# IoT_Greenhouse_V1_0_A_-_Esp32.net
KiCad netlist of a schematic drawn in Altium Designer
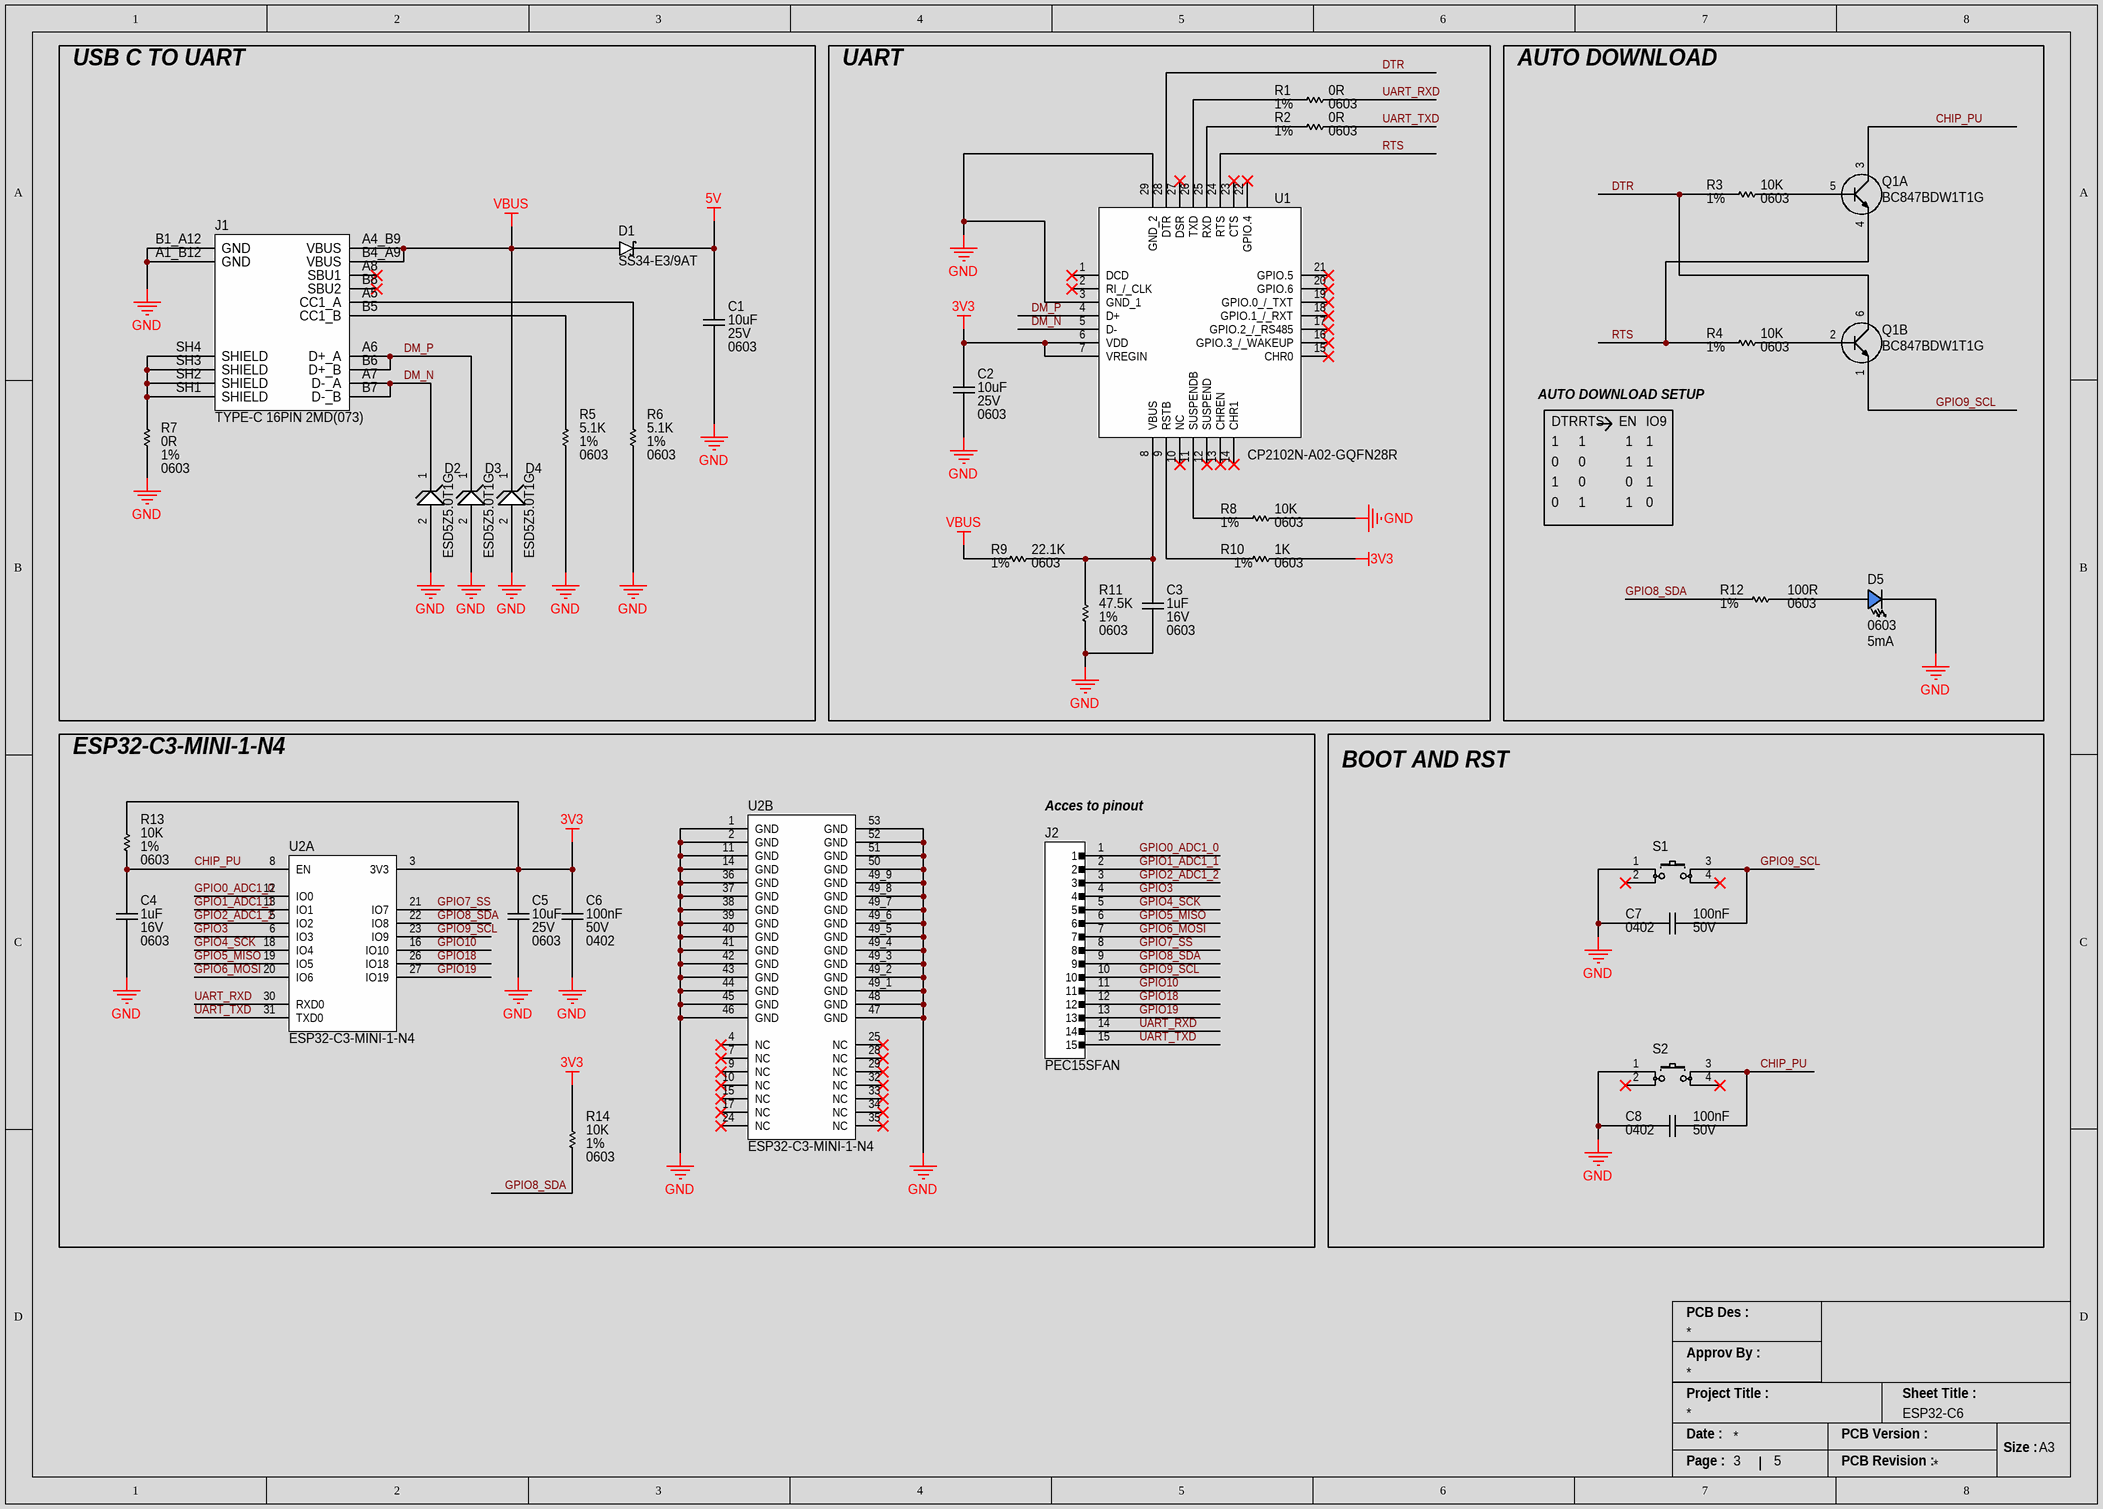
[diagram p0: IoT_Greenhouse V1.0 A - Esp32.SchDoc]

(export (version "E")
  (design (tool "Eeschema 10.0.6"))
  (components
    (comp (ref "C1")
      (value "GRM188R61E106MA73D")
      (footprint "CAP_0603_CAPC1608X08N")
      (description "Multilayer Ceramic Capacitor, 10 uF, 25 V, ± 20%, X5R, 0603 [1608 Metric]")
      (fields
        (field (name "MANUFACTURER") "Murata")
        (field (name "TOLERANCE") "20%")
        (field (name "CASE/PACKAGE") "0603")
        (field (name "CAPACITANCE") "10uF")
        (field (name "VOLTAGE RATING") "25V")
      )
      (libsource (lib "Electronic Devices_LIB") (part "CAP_10UF_25V_X5R_0603"))
    )
    (comp (ref "C2")
      (value "GRM188R61E106MA73D")
      (footprint "CAP_0603_CAPC1608X08N")
      (description "Multilayer Ceramic Capacitor, 10 uF, 25 V, ± 20%, X5R, 0603 [1608 Metric]")
      (fields
        (field (name "MANUFACTURER") "Murata")
        (field (name "TOLERANCE") "20%")
        (field (name "CASE/PACKAGE") "0603")
        (field (name "CAPACITANCE") "10uF")
        (field (name "VOLTAGE RATING") "25V")
      )
      (libsource (lib "Electronic Devices_LIB") (part "CAP_10UF_25V_X5R_0603"))
    )
    (comp (ref "C3")
      (value "CL10A105KO8NNNC")
      (footprint "CAP_0603_CAPC1608X08N")
      (description "CAP CER 1UF 16V X5R 0603")
      (fields
        (field (name "MANUFACTURER") "Samsung")
        (field (name "TOLERANCE") "10%")
        (field (name "VOLTAGE RATING") "16V")
        (field (name "CAPACITANCE") "1uF")
        (field (name "CASE/PACKAGE") "0603")
      )
      (libsource (lib "Electronic Devices_LIB") (part "CAP_1UF_16V_X5R_0603"))
    )
    (comp (ref "C4")
      (value "CL10A105KO8NNNC")
      (footprint "CAP_0603_CAPC1608X08N")
      (description "CAP CER 1UF 16V X5R 0603")
      (fields
        (field (name "MANUFACTURER") "Samsung")
        (field (name "TOLERANCE") "10%")
        (field (name "VOLTAGE RATING") "16V")
        (field (name "CAPACITANCE") "1uF")
        (field (name "CASE/PACKAGE") "0603")
      )
      (libsource (lib "Electronic Devices_LIB") (part "CAP_1UF_16V_X5R_0603"))
    )
    (comp (ref "C5")
      (value "GRM188R61E106MA73D")
      (footprint "CAP_0603_CAPC1608X08N")
      (description "Multilayer Ceramic Capacitor, 10 uF, 25 V, ± 20%, X5R, 0603 [1608 Metric]")
      (fields
        (field (name "MANUFACTURER") "Murata")
        (field (name "TOLERANCE") "20%")
        (field (name "CASE/PACKAGE") "0603")
        (field (name "CAPACITANCE") "10uF")
        (field (name "VOLTAGE RATING") "25V")
      )
      (libsource (lib "Electronic Devices_LIB") (part "CAP_10UF_25V_X5R_0603"))
    )
    (comp (ref "C6")
      (value "GRM155R71H104KE14D")
      (footprint "CAP_0402_CAPC1005X05N")
      (description "Multilayer Ceramic Capacitor, 0.1 uF, 16 V, ± 10%, X7R, 0402 [1005 Metric]")
      (fields
        (field (name "MANUFACTURER") "Murata")
        (field (name "TOLERANCE") "10%")
        (field (name "VOLTAGE RATING") "50V")
        (field (name "CAPACITANCE") "100nF")
        (field (name "CASE/PACKAGE") "0402")
      )
      (libsource (lib "Electronic Devices_LIB") (part "CAP_100NF_50V_X7R_0402"))
    )
    (comp (ref "C7")
      (value "GRM155R71H104KE14D")
      (footprint "CAP_0402_CAPC1005X05N")
      (description "Multilayer Ceramic Capacitor, 0.1 uF, 16 V, ± 10%, X7R, 0402 [1005 Metric]")
      (fields
        (field (name "MANUFACTURER") "Murata")
        (field (name "TOLERANCE") "10%")
        (field (name "VOLTAGE RATING") "50V")
        (field (name "CAPACITANCE") "100nF")
        (field (name "CASE/PACKAGE") "0402")
      )
      (libsource (lib "Electronic Devices_LIB") (part "CAP_100NF_50V_X7R_0402"))
    )
    (comp (ref "C8")
      (value "GRM155R71H104KE14D")
      (footprint "CAP_0402_CAPC1005X05N")
      (description "Multilayer Ceramic Capacitor, 0.1 uF, 16 V, ± 10%, X7R, 0402 [1005 Metric]")
      (fields
        (field (name "MANUFACTURER") "Murata")
        (field (name "TOLERANCE") "10%")
        (field (name "VOLTAGE RATING") "50V")
        (field (name "CAPACITANCE") "100nF")
        (field (name "CASE/PACKAGE") "0402")
      )
      (libsource (lib "Electronic Devices_LIB") (part "CAP_100NF_50V_X7R_0402"))
    )
    (comp (ref "D1")
      (value "SS34-E3/9AT")
      (footprint "DIO_Vishay_SMC_MFG")
      (description "Rectifier Diode, schottky, 40V V(Rrm), do-214Ab / Smc")
      (fields (field (name "MANUFACTURER") "Vishay Semiconductors"))
      (libsource (lib "Electronic Devices_LIB") (part "DIO_SCTKY_40V_3A"))
    )
    (comp (ref "D2")
      (value "ESD5Z5.0T1G")
      (footprint "SOD523_SODFL1608X70N")
      (description "ESD5Z Series 6.2 V 80 pF 5 Vrwm TVS and ESD Protection Diodes - SOD-523")
      (fields (field (name "MANUFACTURER") "ON Semiconductor"))
      (libsource (lib "Electronic Devices_LIB") (part "DIO_TVS_5V_ESD5Z5.0T1G"))
    )
    (comp (ref "D3")
      (value "ESD5Z5.0T1G")
      (footprint "SOD523_SODFL1608X70N")
      (description "ESD5Z Series 6.2 V 80 pF 5 Vrwm TVS and ESD Protection Diodes - SOD-523")
      (fields (field (name "MANUFACTURER") "ON Semiconductor"))
      (libsource (lib "Electronic Devices_LIB") (part "DIO_TVS_5V_ESD5Z5.0T1G"))
    )
    (comp (ref "D4")
      (value "ESD5Z5.0T1G")
      (footprint "SOD523_SODFL1608X70N")
      (description "ESD5Z Series 6.2 V 80 pF 5 Vrwm TVS and ESD Protection Diodes - SOD-523")
      (fields (field (name "MANUFACTURER") "ON Semiconductor"))
      (libsource (lib "Electronic Devices_LIB") (part "DIO_TVS_5V_ESD5Z5.0T1G"))
    )
    (comp (ref "D5")
      (value "LTST-C193TBKT-5A")
      (footprint "LED_0603-BLUE-0.75mm")
      (description "LED Uni-Color Blue 468nm 2-Pin Chip LED T/R")
      (fields
        (field (name "MANUFACTURER") "Vishay Lite-On")
        (field (name "CASE CODE (IMPERIAL)") "0603")
        (field (name "TEST CURRENT") "5mA")
      )
      (libsource (lib "Electronic Devices_LIB") (part "LED_DIO_BLUE_5mA_0603"))
    )
    (comp (ref "J1")
      (value "TYPE-C 16PIN 2MD(073)")
      (footprint "CONN_USB_C_16P")
      (description "5A 1 Surface Mount 16P Female -25℃~+85℃ Type-C SMD USB Connectors ROHS")
      (fields (field (name "MANUFACTURER") "SHOU HAN"))
      (libsource (lib "Electronic Devices_LIB") (part "CONN_USB_TYPEC_2.0_16P_TYPE-C 16PIN 2MD(073)"))
    )
    (comp (ref "J2")
      (value "PEC15SFAN")
      (footprint "HEADER_MALE_15P")
      (description "CONN HEADER .100 SINGL STR 15POS")
      (fields (field (name "MANUFACTURER") "Sullins"))
      (libsource (lib "Electronic Devices_LIB") (part "CONN_HEADER_MALE_15P_2.54mm"))
    )
    (comp (ref "Q1")
      (value "BC847BDW1T1G")
      (footprint "TRANS_BJT_SOT65P210X110-6N")
      (description "ON Semi BC847BDW1T1G Dual NPN Bipolar Transistor; 0.1 A; 45 V; 6-Pin SC-88")
      (fields (field (name "MANUFACTURER") "ON Semiconductor"))
      (libsource (lib "Electronic Devices_LIB") (part "TRANS_BIPOLAR_NPN_BC847BDW1T1G"))
    )
    (comp (ref "R1")
      (value "RC0603FR-070RL")
      (footprint "RES_0603_RESC1608X04N")
      (description "RC Series 0603 0.1 W 0 Ohm Jumper Surface Mount Thick Film Chip Resistor")
      (fields
        (field (name "MANUFACTURER") "Yageo")
        (field (name "TOLERANCE") "1%")
        (field (name "RESISTANCE") "0R")
        (field (name "CASE CODE (IMPERIAL)") "0603")
      )
      (libsource (lib "Electronic Devices_LIB") (part "RES_0R_1%_100mW_0603"))
    )
    (comp (ref "R2")
      (value "RC0603FR-070RL")
      (footprint "RES_0603_RESC1608X04N")
      (description "RC Series 0603 0.1 W 0 Ohm Jumper Surface Mount Thick Film Chip Resistor")
      (fields
        (field (name "MANUFACTURER") "Yageo")
        (field (name "TOLERANCE") "1%")
        (field (name "RESISTANCE") "0R")
        (field (name "CASE CODE (IMPERIAL)") "0603")
      )
      (libsource (lib "Electronic Devices_LIB") (part "RES_0R_1%_100mW_0603"))
    )
    (comp (ref "R3")
      (value "AC0603FR-1010KL")
      (footprint "RES_0603_RESC1608X04N")
      (description "Chip Resistor Automotive Grade Thick Film 0603 10kOhm 1% Paper T/R")
      (fields
        (field (name "MANUFACTURER") "Yageo")
        (field (name "RESISTANCE") "10K")
        (field (name "TOLERANCE") "1%")
        (field (name "CASE/PACKAGE") "0603")
      )
      (libsource (lib "Electronic Devices_LIB") (part "RES_10K_1%_100mW_0603"))
    )
    (comp (ref "R4")
      (value "AC0603FR-1010KL")
      (footprint "RES_0603_RESC1608X04N")
      (description "Chip Resistor Automotive Grade Thick Film 0603 10kOhm 1% Paper T/R")
      (fields
        (field (name "MANUFACTURER") "Yageo")
        (field (name "RESISTANCE") "10K")
        (field (name "TOLERANCE") "1%")
        (field (name "CASE/PACKAGE") "0603")
      )
      (libsource (lib "Electronic Devices_LIB") (part "RES_10K_1%_100mW_0603"))
    )
    (comp (ref "R5")
      (value "RC0603FR-075K1L")
      (footprint "RES_0603_RESC1608X04N")
      (description "SMD Chip Resistor, 5.1 kOhm, ± 1%, 100 mW, 0603 [1608 Metric], Thick Film, General Purpose")
      (fields
        (field (name "MANUFACTURER") "Yageo")
        (field (name "TOLERANCE") "1%")
        (field (name "RESISTANCE") "5.1K")
        (field (name "CASE/PACKAGE") "0603")
      )
      (libsource (lib "Electronic Devices_LIB") (part "RES_5.1K_1%_100mW_0603"))
    )
    (comp (ref "R6")
      (value "RC0603FR-075K1L")
      (footprint "RES_0603_RESC1608X04N")
      (description "SMD Chip Resistor, 5.1 kOhm, ± 1%, 100 mW, 0603 [1608 Metric], Thick Film, General Purpose")
      (fields
        (field (name "MANUFACTURER") "Yageo")
        (field (name "TOLERANCE") "1%")
        (field (name "RESISTANCE") "5.1K")
        (field (name "CASE/PACKAGE") "0603")
      )
      (libsource (lib "Electronic Devices_LIB") (part "RES_5.1K_1%_100mW_0603"))
    )
    (comp (ref "R7")
      (value "RC0603FR-070RL")
      (footprint "RES_0603_RESC1608X04N")
      (description "RC Series 0603 0.1 W 0 Ohm Jumper Surface Mount Thick Film Chip Resistor")
      (fields
        (field (name "MANUFACTURER") "Yageo")
        (field (name "TOLERANCE") "1%")
        (field (name "RESISTANCE") "0R")
        (field (name "CASE CODE (IMPERIAL)") "0603")
      )
      (libsource (lib "Electronic Devices_LIB") (part "RES_0R_1%_100mW_0603"))
    )
    (comp (ref "R8")
      (value "AC0603FR-1010KL")
      (footprint "RES_0603_RESC1608X04N")
      (description "Chip Resistor Automotive Grade Thick Film 0603 10kOhm 1% Paper T/R")
      (fields
        (field (name "MANUFACTURER") "Yageo")
        (field (name "RESISTANCE") "10K")
        (field (name "TOLERANCE") "1%")
        (field (name "CASE/PACKAGE") "0603")
      )
      (libsource (lib "Electronic Devices_LIB") (part "RES_10K_1%_100mW_0603"))
    )
    (comp (ref "R9")
      (value "RC0603FR-0722K1L")
      (footprint "RES_0603_RESC1608X04N")
      (description "SMD Chip Resistor, 22.1 kOhm, ± 1%, 100 mW, 0603 [1608 Metric], Thick Film, General Purpose")
      (fields
        (field (name "MANUFACTURER") "Yageo")
        (field (name "RESISTANCE") "22.1K")
        (field (name "TOLERANCE") "1%")
        (field (name "CASE/PACKAGE") "0603")
      )
      (libsource (lib "Electronic Devices_LIB") (part "RES_22.1K_1%_100mW_0603"))
    )
    (comp (ref "R10")
      (value "AC0603FR-101KL")
      (footprint "RES_0603_RESC1608X04N")
      (description "Chip Resistor Automotive Grade Thick Film 0603 1kOhm 1% Paper T/R")
      (fields
        (field (name "MANUFACTURER") "Yageo")
        (field (name "RESISTANCE") "1K")
        (field (name "TOLERANCE") "1%")
        (field (name "CASE/PACKAGE") "0603")
      )
      (libsource (lib "Electronic Devices_LIB") (part "RES_1K_1%_100mW_0603"))
    )
    (comp (ref "R11")
      (value "AC0603FR-0747K5L")
      (footprint "RES_0603_RESC1608X04N")
      (description "SMD Chip Resistor, 47.5 kOhm, ± 1%, 100 mW, 0603 [1608 Metric], Thick Film, General Purpose")
      (fields
        (field (name "MANUFACTURER") "Yageo")
        (field (name "TOLERANCE") "1%")
        (field (name "RESISTANCE") "47.5K")
        (field (name "CASE/PACKAGE") "0603")
      )
      (libsource (lib "Electronic Devices_LIB") (part "RES_47.5K_1%_100mW_0603"))
    )
    (comp (ref "R12")
      (value "ERJ3EKF1000V")
      (footprint "CAP_0603_CAPC1608X08N")
      (description "Res Thick Film 0603 100 Ohm 1% 1/10W ±100ppm/°C Molded SMD Punched Carrier T/R")
      (fields
        (field (name "MANUFACTURER") "Panasonic")
        (field (name "CASE CODE (IMPERIAL)") "0603")
        (field (name "TOLERANCE") "1%")
        (field (name "RESISTANCE") "100R")
      )
      (libsource (lib "Electronic Devices_LIB") (part "RES_100R_1%_100MW_0603"))
    )
    (comp (ref "R13")
      (value "AC0603FR-1010KL")
      (footprint "RES_0603_RESC1608X04N")
      (description "Chip Resistor Automotive Grade Thick Film 0603 10kOhm 1% Paper T/R")
      (fields
        (field (name "MANUFACTURER") "Yageo")
        (field (name "RESISTANCE") "10K")
        (field (name "TOLERANCE") "1%")
        (field (name "CASE/PACKAGE") "0603")
      )
      (libsource (lib "Electronic Devices_LIB") (part "RES_10K_1%_100mW_0603"))
    )
    (comp (ref "R14")
      (value "AC0603FR-1010KL")
      (footprint "RES_0603_RESC1608X04N")
      (description "Chip Resistor Automotive Grade Thick Film 0603 10kOhm 1% Paper T/R")
      (fields
        (field (name "MANUFACTURER") "Yageo")
        (field (name "RESISTANCE") "10K")
        (field (name "TOLERANCE") "1%")
        (field (name "CASE/PACKAGE") "0603")
      )
      (libsource (lib "Electronic Devices_LIB") (part "RES_10K_1%_100mW_0603"))
    )
    (comp (ref "S1")
      (value "PTS526SK15SMTR2LFS")
      (footprint "SWT_NO_PTS526SK15SMTR2LFS")
      (description "Switch Tactile N.O. SPST Round Button Gull Wing 0.05A 12VDC 200000Cycles 2.55N SMD T/R")
      (fields (field (name "MANUFACTURER") "ITT C&K"))
      (libsource (lib "Electronic Devices_LIB") (part "SWITCH_NO_SPST_0.05A"))
    )
    (comp (ref "S2")
      (value "PTS526SK15SMTR2LFS")
      (footprint "SWT_NO_PTS526SK15SMTR2LFS")
      (description "Switch Tactile N.O. SPST Round Button Gull Wing 0.05A 12VDC 200000Cycles 2.55N SMD T/R")
      (fields (field (name "MANUFACTURER") "ITT C&K"))
      (libsource (lib "Electronic Devices_LIB") (part "SWITCH_NO_SPST_0.05A"))
    )
    (comp (ref "U1")
      (value "CP2102N-A02-GQFN28R")
      (footprint "IC_BRIDGE_UART_QFN50P500X500X80-29N-D")
      (description "Full Speed USB to UART Bridge USB 2.0 3.3V T/R Automotive 28-Pin QFN EP")
      (fields (field (name "MANUFACTURER") "Silicon Labs"))
      (libsource (lib "Electronic Devices_LIB") (part "IC_BRIDGE_UART_CP2102N-A02-GQFN28R"))
    )
    (comp (ref "U2")
      (value "ESP32-C3-MINI-1-N4")
      (footprint "XCVR_ESP32-C3-MINI-1-N4")
      (description "Multiprotocol Modules SMD module, ESP32-C3FN4, PCB antenna, -40 C +85 C")
      (fields (field (name "MANUFACTURER") "Espressif Systems"))
      (libsource (lib "Electronic Devices_LIB") (part "IC_MODULE_ESP32-C3-MINI-1-N4"))
    )
  )
  (nets
    (net (code "1") (name "/CHIP_PU") (class "Default")
      (node (ref "C4") (pin "2") (pinfunction "2_2") (pintype "passive"))
      (node (ref "C8") (pin "1") (pinfunction "1_1") (pintype "passive"))
      (node (ref "Q1") (pin "3") (pinfunction "COLLECTOR_1_3") (pintype "passive"))
      (node (ref "R13") (pin "2") (pinfunction "2_2") (pintype "passive"))
      (node (ref "S2") (pin "3") (pinfunction "NO1_3") (pintype "passive"))
      (node (ref "U2") (pin "8") (pinfunction "EN_8") (pintype "passive"))
    )
    (net (code "2") (name "/DM_N") (class "Default")
      (node (ref "D2") (pin "1") (pinfunction "K_1") (pintype "passive"))
      (node (ref "J1") (pin "A7") (pinfunction "D-_A_A7") (pintype "passive"))
      (node (ref "J1") (pin "B7") (pinfunction "D-_B_B7") (pintype "passive"))
      (node (ref "U1") (pin "5") (pinfunction "D-_5") (pintype "passive"))
    )
    (net (code "3") (name "/DM_P") (class "Default")
      (node (ref "D3") (pin "1") (pinfunction "K_1") (pintype "passive"))
      (node (ref "J1") (pin "A6") (pinfunction "D+_A_A6") (pintype "passive"))
      (node (ref "J1") (pin "B6") (pinfunction "D+_B_B6") (pintype "passive"))
      (node (ref "U1") (pin "4") (pinfunction "D+_4") (pintype "passive"))
    )
    (net (code "4") (name "/DTR") (class "Default")
      (node (ref "Q1") (pin "6") (pinfunction "COLLECTOR_2_6") (pintype "passive"))
      (node (ref "R3") (pin "2") (pinfunction "2_2") (pintype "passive"))
      (node (ref "U1") (pin "28") (pinfunction "DTR_28") (pintype "passive"))
    )
    (net (code "5") (name "/GPIO0_ADC1_0") (class "Default")
      (node (ref "J2") (pin "1") (pinfunction "1_1") (pintype "passive"))
      (node (ref "U2") (pin "12") (pinfunction "IO0_12") (pintype "passive"))
    )
    (net (code "6") (name "/GPIO1_ADC1_1") (class "Default")
      (node (ref "J2") (pin "2") (pinfunction "2_2") (pintype "passive"))
      (node (ref "U2") (pin "13") (pinfunction "IO1_13") (pintype "passive"))
    )
    (net (code "7") (name "/GPIO2_ADC1_2") (class "Default")
      (node (ref "J2") (pin "3") (pinfunction "3_3") (pintype "passive"))
      (node (ref "U2") (pin "5") (pinfunction "IO2_5") (pintype "passive"))
    )
    (net (code "8") (name "/GPIO3") (class "Default")
      (node (ref "J2") (pin "4") (pinfunction "4_4") (pintype "passive"))
      (node (ref "U2") (pin "6") (pinfunction "IO3_6") (pintype "passive"))
    )
    (net (code "9") (name "/GPIO4_SCK") (class "Default")
      (node (ref "J2") (pin "5") (pinfunction "5_5") (pintype "passive"))
      (node (ref "U2") (pin "18") (pinfunction "IO4_18") (pintype "passive"))
    )
    (net (code "10") (name "/GPIO5_MISO") (class "Default")
      (node (ref "J2") (pin "6") (pinfunction "6_6") (pintype "passive"))
      (node (ref "U2") (pin "19") (pinfunction "IO5_19") (pintype "passive"))
    )
    (net (code "11") (name "/GPIO6_MOSI") (class "Default")
      (node (ref "J2") (pin "7") (pinfunction "7_7") (pintype "passive"))
      (node (ref "U2") (pin "20") (pinfunction "IO6_20") (pintype "passive"))
    )
    (net (code "12") (name "/GPIO7_SS") (class "Default")
      (node (ref "J2") (pin "8") (pinfunction "8_8") (pintype "passive"))
      (node (ref "U2") (pin "21") (pinfunction "IO7_21") (pintype "passive"))
    )
    (net (code "13") (name "/GPIO8_SDA") (class "Default")
      (node (ref "J2") (pin "9") (pinfunction "9_9") (pintype "passive"))
      (node (ref "R12") (pin "1") (pinfunction "1_1") (pintype "passive"))
      (node (ref "R14") (pin "2") (pinfunction "2_2") (pintype "passive"))
      (node (ref "U2") (pin "22") (pinfunction "IO8_22") (pintype "passive"))
    )
    (net (code "14") (name "/GPIO9_SCL") (class "Default")
      (node (ref "C7") (pin "1") (pinfunction "1_1") (pintype "passive"))
      (node (ref "J2") (pin "10") (pinfunction "10_10") (pintype "passive"))
      (node (ref "Q1") (pin "1") (pinfunction "EMITTER_2_1") (pintype "passive"))
      (node (ref "S1") (pin "3") (pinfunction "NO1_3") (pintype "passive"))
      (node (ref "U2") (pin "23") (pinfunction "IO9_23") (pintype "passive"))
    )
    (net (code "15") (name "/GPIO10") (class "Default")
      (node (ref "J2") (pin "11") (pinfunction "11_11") (pintype "passive"))
      (node (ref "U2") (pin "16") (pinfunction "IO10_16") (pintype "passive"))
    )
    (net (code "16") (name "/GPIO18") (class "Default")
      (node (ref "J2") (pin "12") (pinfunction "12_12") (pintype "passive"))
      (node (ref "U2") (pin "26") (pinfunction "IO18_26") (pintype "passive"))
    )
    (net (code "17") (name "/GPIO19") (class "Default")
      (node (ref "J2") (pin "13") (pinfunction "13_13") (pintype "passive"))
      (node (ref "U2") (pin "27") (pinfunction "IO19_27") (pintype "passive"))
    )
    (net (code "18") (name "/RTS") (class "Default")
      (node (ref "Q1") (pin "4") (pinfunction "EMITTER_1_4") (pintype "passive"))
      (node (ref "R4") (pin "2") (pinfunction "2_2") (pintype "passive"))
      (node (ref "U1") (pin "24") (pinfunction "RTS_24") (pintype "passive"))
    )
    (net (code "19") (name "/UART_RXD") (class "Default")
      (node (ref "J2") (pin "14") (pinfunction "14_14") (pintype "passive"))
      (node (ref "R1") (pin "1") (pinfunction "1_1") (pintype "passive"))
      (node (ref "U2") (pin "30") (pinfunction "RXD0_30") (pintype "passive"))
    )
    (net (code "20") (name "/UART_TXD") (class "Default")
      (node (ref "J2") (pin "15") (pinfunction "15_15") (pintype "passive"))
      (node (ref "R2") (pin "1") (pinfunction "1_1") (pintype "passive"))
      (node (ref "U2") (pin "31") (pinfunction "TXD0_31") (pintype "passive"))
    )
    (net (code "21") (name "3V3") (class "Default")
      (node (ref "C2") (pin "2") (pinfunction "2_2") (pintype "passive"))
      (node (ref "C5") (pin "2") (pinfunction "2_2") (pintype "passive"))
      (node (ref "C6") (pin "2") (pinfunction "2_2") (pintype "passive"))
      (node (ref "R10") (pin "2") (pinfunction "2_2") (pintype "passive"))
      (node (ref "R13") (pin "1") (pinfunction "1_1") (pintype "passive"))
      (node (ref "R14") (pin "1") (pinfunction "1_1") (pintype "passive"))
      (node (ref "U1") (pin "6") (pinfunction "VDD_6") (pintype "passive"))
      (node (ref "U1") (pin "7") (pinfunction "VREGIN_7") (pintype "passive"))
      (node (ref "U2") (pin "3") (pinfunction "3V3_3") (pintype "passive"))
    )
    (net (code "22") (name "5V") (class "Default")
      (node (ref "C1") (pin "2") (pinfunction "2_2") (pintype "passive"))
      (node (ref "D1") (pin "1") (pinfunction "K_1") (pintype "passive"))
    )
    (net (code "23") (name "GND") (class "Default")
      (node (ref "C1") (pin "1") (pinfunction "1_1") (pintype "passive"))
      (node (ref "C2") (pin "1") (pinfunction "1_1") (pintype "passive"))
      (node (ref "C3") (pin "1") (pinfunction "1_1") (pintype "passive"))
      (node (ref "C4") (pin "1") (pinfunction "1_1") (pintype "passive"))
      (node (ref "C5") (pin "1") (pinfunction "1_1") (pintype "passive"))
      (node (ref "C6") (pin "1") (pinfunction "1_1") (pintype "passive"))
      (node (ref "C7") (pin "2") (pinfunction "2_2") (pintype "passive"))
      (node (ref "C8") (pin "2") (pinfunction "2_2") (pintype "passive"))
      (node (ref "D2") (pin "2") (pinfunction "A_2") (pintype "passive"))
      (node (ref "D3") (pin "2") (pinfunction "A_2") (pintype "passive"))
      (node (ref "D4") (pin "2") (pinfunction "A_2") (pintype "passive"))
      (node (ref "D5") (pin "1") (pinfunction "C_1") (pintype "passive"))
      (node (ref "J1") (pin "A1_B12") (pinfunction "GND_A1_B12") (pintype "power_in"))
      (node (ref "J1") (pin "B1_A12") (pinfunction "GND_B1_A12") (pintype "power_in"))
      (node (ref "R11") (pin "1") (pinfunction "1_1") (pintype "passive"))
      (node (ref "R5") (pin "1") (pinfunction "1_1") (pintype "passive"))
      (node (ref "R6") (pin "1") (pinfunction "1_1") (pintype "passive"))
      (node (ref "R7") (pin "1") (pinfunction "1_1") (pintype "passive"))
      (node (ref "R8") (pin "2") (pinfunction "2_2") (pintype "passive"))
      (node (ref "S1") (pin "1") (pinfunction "COM_1_1") (pintype "passive"))
      (node (ref "S2") (pin "1") (pinfunction "COM_1_1") (pintype "passive"))
      (node (ref "U1") (pin "29") (pinfunction "GND_2_29") (pintype "passive"))
      (node (ref "U1") (pin "3") (pinfunction "GND_1_3") (pintype "passive"))
      (node (ref "U2") (pin "1") (pinfunction "GND_1") (pintype "power_in"))
      (node (ref "U2") (pin "11") (pinfunction "GND_11") (pintype "power_in"))
      (node (ref "U2") (pin "14") (pinfunction "GND_14") (pintype "power_in"))
      (node (ref "U2") (pin "2") (pinfunction "GND_2") (pintype "power_in"))
      (node (ref "U2") (pin "36") (pinfunction "GND_36") (pintype "power_in"))
      (node (ref "U2") (pin "37") (pinfunction "GND_37") (pintype "power_in"))
      (node (ref "U2") (pin "38") (pinfunction "GND_38") (pintype "power_in"))
      (node (ref "U2") (pin "39") (pinfunction "GND_39") (pintype "power_in"))
      (node (ref "U2") (pin "40") (pinfunction "GND_40") (pintype "power_in"))
      (node (ref "U2") (pin "41") (pinfunction "GND_41") (pintype "power_in"))
      (node (ref "U2") (pin "42") (pinfunction "GND_42") (pintype "power_in"))
      (node (ref "U2") (pin "43") (pinfunction "GND_43") (pintype "power_in"))
      (node (ref "U2") (pin "44") (pinfunction "GND_44") (pintype "power_in"))
      (node (ref "U2") (pin "45") (pinfunction "GND_45") (pintype "power_in"))
      (node (ref "U2") (pin "46") (pinfunction "GND_46") (pintype "power_in"))
      (node (ref "U2") (pin "47") (pinfunction "GND_47") (pintype "power_in"))
      (node (ref "U2") (pin "48") (pinfunction "GND_48") (pintype "power_in"))
      (node (ref "U2") (pin "49_1") (pinfunction "GND_49_1") (pintype "power_in"))
      (node (ref "U2") (pin "49_2") (pinfunction "GND_49_2") (pintype "power_in"))
      (node (ref "U2") (pin "49_3") (pinfunction "GND_49_3") (pintype "power_in"))
      (node (ref "U2") (pin "49_4") (pinfunction "GND_49_4") (pintype "power_in"))
      (node (ref "U2") (pin "49_5") (pinfunction "GND_49_5") (pintype "power_in"))
      (node (ref "U2") (pin "49_6") (pinfunction "GND_49_6") (pintype "power_in"))
      (node (ref "U2") (pin "49_7") (pinfunction "GND_49_7") (pintype "power_in"))
      (node (ref "U2") (pin "49_8") (pinfunction "GND_49_8") (pintype "power_in"))
      (node (ref "U2") (pin "49_9") (pinfunction "GND_49_9") (pintype "power_in"))
      (node (ref "U2") (pin "50") (pinfunction "GND_50") (pintype "power_in"))
      (node (ref "U2") (pin "51") (pinfunction "GND_51") (pintype "power_in"))
      (node (ref "U2") (pin "52") (pinfunction "GND_52") (pintype "power_in"))
      (node (ref "U2") (pin "53") (pinfunction "GND_53") (pintype "power_in"))
    )
    (net (code "24") (name "Net-(D5-A)") (class "Default")
      (node (ref "D5") (pin "2") (pinfunction "A_2") (pintype "passive"))
      (node (ref "R12") (pin "2") (pinfunction "2_2") (pintype "passive"))
    )
    (net (code "25") (name "Net-(J1-CC1_A)") (class "Default")
      (node (ref "J1") (pin "A5") (pinfunction "CC1_A_A5") (pintype "passive"))
      (node (ref "R6") (pin "2") (pinfunction "2_2") (pintype "passive"))
    )
    (net (code "26") (name "Net-(J1-CC1_B)") (class "Default")
      (node (ref "J1") (pin "B5") (pinfunction "CC1_B_B5") (pintype "passive"))
      (node (ref "R5") (pin "2") (pinfunction "2_2") (pintype "passive"))
    )
    (net (code "27") (name "Net-(J1-SHIELD-PadSH1)") (class "Default")
      (node (ref "J1") (pin "SH1") (pinfunction "SHIELD_SH1") (pintype "passive"))
      (node (ref "J1") (pin "SH2") (pinfunction "SHIELD_SH2") (pintype "passive"))
      (node (ref "J1") (pin "SH3") (pinfunction "SHIELD_SH3") (pintype "passive"))
      (node (ref "J1") (pin "SH4") (pinfunction "SHIELD_SH4") (pintype "passive"))
      (node (ref "R7") (pin "2") (pinfunction "2_2") (pintype "passive"))
    )
    (net (code "28") (name "Net-(Q1A-BASE_1)") (class "Default")
      (node (ref "Q1") (pin "5") (pinfunction "BASE_1_5") (pintype "passive"))
      (node (ref "R3") (pin "1") (pinfunction "1_1") (pintype "passive"))
    )
    (net (code "29") (name "Net-(Q1B-BASE_2)") (class "Default")
      (node (ref "Q1") (pin "2") (pinfunction "BASE_2_2") (pintype "passive"))
      (node (ref "R4") (pin "1") (pinfunction "1_1") (pintype "passive"))
    )
    (net (code "30") (name "Net-(U1-RSTB)") (class "Default")
      (node (ref "R10") (pin "1") (pinfunction "1_1") (pintype "passive"))
      (node (ref "U1") (pin "9") (pinfunction "RSTB_9") (pintype "passive"))
    )
    (net (code "31") (name "Net-(U1-RXD)") (class "Default")
      (node (ref "R2") (pin "2") (pinfunction "2_2") (pintype "passive"))
      (node (ref "U1") (pin "25") (pinfunction "RXD_25") (pintype "passive"))
    )
    (net (code "32") (name "Net-(U1-SUSPENDB)") (class "Default")
      (node (ref "R8") (pin "1") (pinfunction "1_1") (pintype "passive"))
      (node (ref "U1") (pin "11") (pinfunction "SUSPENDB_11") (pintype "passive"))
    )
    (net (code "33") (name "Net-(U1-TXD)") (class "Default")
      (node (ref "R1") (pin "2") (pinfunction "2_2") (pintype "passive"))
      (node (ref "U1") (pin "26") (pinfunction "TXD_26") (pintype "passive"))
    )
    (net (code "34") (name "Net-(U1-VBUS)") (class "Default")
      (node (ref "C3") (pin "2") (pinfunction "2_2") (pintype "passive"))
      (node (ref "R11") (pin "2") (pinfunction "2_2") (pintype "passive"))
      (node (ref "R9") (pin "2") (pinfunction "2_2") (pintype "passive"))
      (node (ref "U1") (pin "8") (pinfunction "VBUS_8") (pintype "passive"))
    )
    (net (code "35") (name "VBUS") (class "Default")
      (node (ref "D1") (pin "2") (pinfunction "A_2") (pintype "passive"))
      (node (ref "D4") (pin "1") (pinfunction "K_1") (pintype "passive"))
      (node (ref "J1") (pin "A4_B9") (pinfunction "VBUS_A4_B9") (pintype "power_in"))
      (node (ref "J1") (pin "B4_A9") (pinfunction "VBUS_B4_A9") (pintype "power_in"))
      (node (ref "R9") (pin "1") (pinfunction "1_1") (pintype "passive"))
    )
    (net (code "36") (name "unconnected-(J1-SBU1-PadA8)") (class "Default")
      (node (ref "J1") (pin "A8") (pinfunction "SBU1_A8") (pintype "passive+no_connect"))
    )
    (net (code "37") (name "unconnected-(J1-SBU2-PadB8)") (class "Default")
      (node (ref "J1") (pin "B8") (pinfunction "SBU2_B8") (pintype "passive+no_connect"))
    )
    (net (code "38") (name "unconnected-(S1-COM2-Pad2)") (class "Default")
      (node (ref "S1") (pin "2") (pinfunction "COM2_2") (pintype "passive+no_connect"))
    )
    (net (code "39") (name "unconnected-(S1-NO2-Pad4)") (class "Default")
      (node (ref "S1") (pin "4") (pinfunction "NO2_4") (pintype "passive+no_connect"))
    )
    (net (code "40") (name "unconnected-(S2-COM2-Pad2)") (class "Default")
      (node (ref "S2") (pin "2") (pinfunction "COM2_2") (pintype "passive+no_connect"))
    )
    (net (code "41") (name "unconnected-(S2-NO2-Pad4)") (class "Default")
      (node (ref "S2") (pin "4") (pinfunction "NO2_4") (pintype "passive+no_connect"))
    )
    (net (code "42") (name "unconnected-(U1-CHR0-Pad15)") (class "Default")
      (node (ref "U1") (pin "15") (pinfunction "CHR0_15") (pintype "passive+no_connect"))
    )
    (net (code "43") (name "unconnected-(U1-CHR1-Pad14)") (class "Default")
      (node (ref "U1") (pin "14") (pinfunction "CHR1_14") (pintype "passive+no_connect"))
    )
    (net (code "44") (name "unconnected-(U1-CHREN-Pad13)") (class "Default")
      (node (ref "U1") (pin "13") (pinfunction "CHREN_13") (pintype "passive+no_connect"))
    )
    (net (code "45") (name "unconnected-(U1-CTS-Pad23)") (class "Default")
      (node (ref "U1") (pin "23") (pinfunction "CTS_23") (pintype "passive+no_connect"))
    )
    (net (code "46") (name "unconnected-(U1-DCD-Pad1)") (class "Default")
      (node (ref "U1") (pin "1") (pinfunction "DCD_1") (pintype "passive+no_connect"))
    )
    (net (code "47") (name "unconnected-(U1-DSR-Pad27)") (class "Default")
      (node (ref "U1") (pin "27") (pinfunction "DSR_27") (pintype "passive+no_connect"))
    )
    (net (code "48") (name "unconnected-(U1-GPIO.0_{slash}_TXT-Pad19)") (class "Default")
      (node (ref "U1") (pin "19") (pinfunction "GPIO.0_/_TXT_19") (pintype "passive+no_connect"))
    )
    (net (code "49") (name "unconnected-(U1-GPIO.1_{slash}_RXT-Pad18)") (class "Default")
      (node (ref "U1") (pin "18") (pinfunction "GPIO.1_/_RXT_18") (pintype "passive+no_connect"))
    )
    (net (code "50") (name "unconnected-(U1-GPIO.2_{slash}_RS485-Pad17)") (class "Default")
      (node (ref "U1") (pin "17") (pinfunction "GPIO.2_/_RS485_17") (pintype "passive+no_connect"))
    )
    (net (code "51") (name "unconnected-(U1-GPIO.3_{slash}_WAKEUP-Pad16)") (class "Default")
      (node (ref "U1") (pin "16") (pinfunction "GPIO.3_/_WAKEUP_16") (pintype "passive+no_connect"))
    )
    (net (code "52") (name "unconnected-(U1-GPIO.4-Pad22)") (class "Default")
      (node (ref "U1") (pin "22") (pinfunction "GPIO.4_22") (pintype "passive+no_connect"))
    )
    (net (code "53") (name "unconnected-(U1-GPIO.5-Pad21)") (class "Default")
      (node (ref "U1") (pin "21") (pinfunction "GPIO.5_21") (pintype "passive+no_connect"))
    )
    (net (code "54") (name "unconnected-(U1-GPIO.6-Pad20)") (class "Default")
      (node (ref "U1") (pin "20") (pinfunction "GPIO.6_20") (pintype "passive+no_connect"))
    )
    (net (code "55") (name "unconnected-(U1-NC-Pad10)") (class "Default")
      (node (ref "U1") (pin "10") (pinfunction "NC_10") (pintype "passive+no_connect"))
    )
    (net (code "56") (name "unconnected-(U1-RI_{slash}_CLK-Pad2)") (class "Default")
      (node (ref "U1") (pin "2") (pinfunction "RI_/_CLK_2") (pintype "passive+no_connect"))
    )
    (net (code "57") (name "unconnected-(U1-SUSPEND-Pad12)") (class "Default")
      (node (ref "U1") (pin "12") (pinfunction "SUSPEND_12") (pintype "passive+no_connect"))
    )
    (net (code "58") (name "unconnected-(U2B-NC-Pad4)") (class "Default")
      (node (ref "U2") (pin "4") (pinfunction "NC_4") (pintype "passive+no_connect"))
    )
    (net (code "59") (name "unconnected-(U2B-NC-Pad7)") (class "Default")
      (node (ref "U2") (pin "7") (pinfunction "NC_7") (pintype "passive+no_connect"))
    )
    (net (code "60") (name "unconnected-(U2B-NC-Pad9)") (class "Default")
      (node (ref "U2") (pin "9") (pinfunction "NC_9") (pintype "passive+no_connect"))
    )
    (net (code "61") (name "unconnected-(U2B-NC-Pad10)") (class "Default")
      (node (ref "U2") (pin "10") (pinfunction "NC_10") (pintype "passive+no_connect"))
    )
    (net (code "62") (name "unconnected-(U2B-NC-Pad15)") (class "Default")
      (node (ref "U2") (pin "15") (pinfunction "NC_15") (pintype "passive+no_connect"))
    )
    (net (code "63") (name "unconnected-(U2B-NC-Pad17)") (class "Default")
      (node (ref "U2") (pin "17") (pinfunction "NC_17") (pintype "passive+no_connect"))
    )
    (net (code "64") (name "unconnected-(U2B-NC-Pad24)") (class "Default")
      (node (ref "U2") (pin "24") (pinfunction "NC_24") (pintype "passive+no_connect"))
    )
    (net (code "65") (name "unconnected-(U2B-NC-Pad25)") (class "Default")
      (node (ref "U2") (pin "25") (pinfunction "NC_25") (pintype "passive+no_connect"))
    )
    (net (code "66") (name "unconnected-(U2B-NC-Pad28)") (class "Default")
      (node (ref "U2") (pin "28") (pinfunction "NC_28") (pintype "passive+no_connect"))
    )
    (net (code "67") (name "unconnected-(U2B-NC-Pad29)") (class "Default")
      (node (ref "U2") (pin "29") (pinfunction "NC_29") (pintype "passive+no_connect"))
    )
    (net (code "68") (name "unconnected-(U2B-NC-Pad32)") (class "Default")
      (node (ref "U2") (pin "32") (pinfunction "NC_32") (pintype "passive+no_connect"))
    )
    (net (code "69") (name "unconnected-(U2B-NC-Pad33)") (class "Default")
      (node (ref "U2") (pin "33") (pinfunction "NC_33") (pintype "passive+no_connect"))
    )
    (net (code "70") (name "unconnected-(U2B-NC-Pad34)") (class "Default")
      (node (ref "U2") (pin "34") (pinfunction "NC_34") (pintype "passive+no_connect"))
    )
    (net (code "71") (name "unconnected-(U2B-NC-Pad35)") (class "Default")
      (node (ref "U2") (pin "35") (pinfunction "NC_35") (pintype "passive+no_connect"))
    )
  )
)
